# supply_filter.net
KiCad netlist of a schematic drawn in Altium Designer
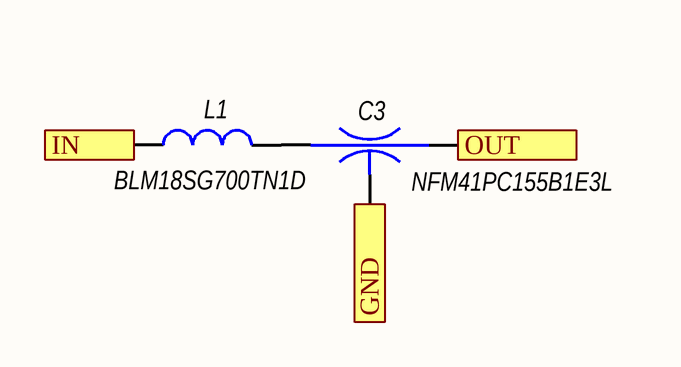
[diagram p0: supply_filter.SchDoc]

(export (version "E")
  (design (tool "Eeschema 10.0.6"))
  (components
    (comp (ref "C3")
      (value "NFM41PC155B1E3L")
      (footprint "FIL_NFM41PC155B1E3L")
      (description "Емкостной фильтр проходной")
      (libsource (lib "SCH_LIB") (part "Capacity_filtr"))
    )
    (comp (ref "L1")
      (value "BLM18SG700TN1D")
      (footprint "RES_0603")
      (description "Дроссель ЭМП")
      (libsource (lib "SCH_LIB") (part "FERRITE_BEAD"))
    )
  )
  (nets
    (net (code "1") (name "/GND") (class "Default") (node (ref "C3") (pin "2") (pintype "passive")))
    (net (code "2") (name "/IN") (class "Default")
      (node (ref "L1") (pin "2") (pinfunction "8_2") (pintype "passive"))
    )
    (net (code "3") (name "/OUT") (class "Default") (node (ref "C3") (pin "3") (pintype "passive")))
    (net (code "4") (name "Net-(L1-7)") (class "Default")
      (node (ref "C3") (pin "1") (pintype "passive"))
      (node (ref "L1") (pin "1") (pinfunction "7_1") (pintype "passive"))
    )
  )
)
